# RIO_MCU.net
KiCad netlist of a schematic drawn in Altium Designer
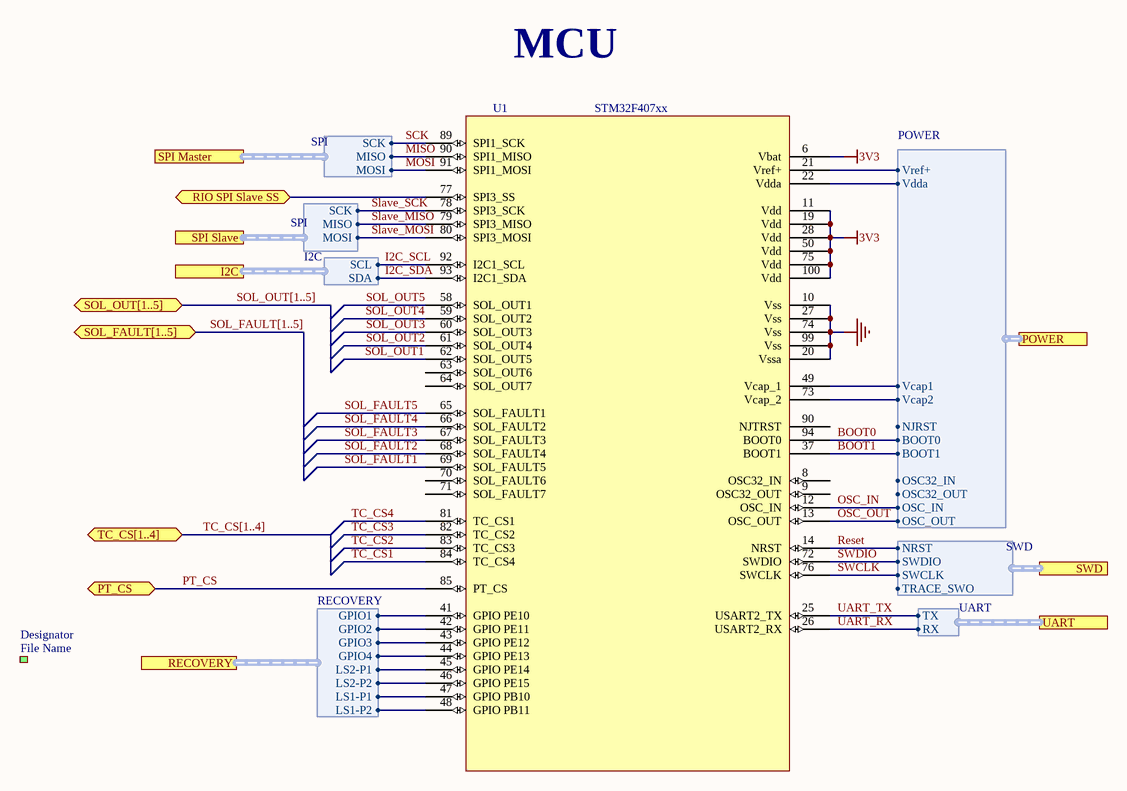
[diagram p0: RIO_MCU.SchDoc]

(export (version "E")
  (design (tool "Eeschema 10.0.6"))
  (components
    (comp (ref "U1")
      (value "STM32F407xx")
      (footprint "LQFP100")
      (libsource (lib "LaunchyRIOComponents") (part "STM32F407xx"))
    )
  )
  (nets
    (net (code "7") (name "/BOOT0") (class "Default")
      (node (ref "U1") (pin "94") (pinfunction "BOOT0_94") (pintype "passive"))
    )
    (net (code "8") (name "/BOOT1") (class "Default")
      (node (ref "U1") (pin "37") (pinfunction "BOOT1_37") (pintype "passive"))
    )
    (net (code "9") (name "/GPIO1") (class "Default")
      (node (ref "U1") (pin "41") (pinfunction "GPIO_PE10_41") (pintype "bidirectional"))
    )
    (net (code "10") (name "/GPIO2") (class "Default")
      (node (ref "U1") (pin "42") (pinfunction "GPIO_PE11_42") (pintype "bidirectional"))
    )
    (net (code "11") (name "/GPIO3") (class "Default")
      (node (ref "U1") (pin "43") (pinfunction "GPIO_PE12_43") (pintype "bidirectional"))
    )
    (net (code "12") (name "/GPIO4") (class "Default")
      (node (ref "U1") (pin "44") (pinfunction "GPIO_PE13_44") (pintype "bidirectional"))
    )
    (net (code "13") (name "/I2C_SCL") (class "Default")
      (node (ref "U1") (pin "92") (pinfunction "I2C1_SCL_92") (pintype "bidirectional"))
    )
    (net (code "14") (name "/I2C_SDA") (class "Default")
      (node (ref "U1") (pin "93") (pinfunction "I2C1_SDA_93") (pintype "bidirectional"))
    )
    (net (code "15") (name "/LS1-P1") (class "Default")
      (node (ref "U1") (pin "47") (pinfunction "GPIO_PB10_47") (pintype "bidirectional"))
    )
    (net (code "16") (name "/LS1-P2") (class "Default")
      (node (ref "U1") (pin "48") (pinfunction "GPIO_PB11_48") (pintype "bidirectional"))
    )
    (net (code "17") (name "/LS2-P1") (class "Default")
      (node (ref "U1") (pin "45") (pinfunction "GPIO_PE14_45") (pintype "bidirectional"))
    )
    (net (code "18") (name "/LS2-P2") (class "Default")
      (node (ref "U1") (pin "46") (pinfunction "GPIO_PE15_46") (pintype "bidirectional"))
    )
    (net (code "19") (name "/MISO") (class "Default")
      (node (ref "U1") (pin "90") (pinfunction "SPI1_MISO_90") (pintype "bidirectional"))
    )
    (net (code "20") (name "/MOSI") (class "Default")
      (node (ref "U1") (pin "91") (pinfunction "SPI1_MOSI_91") (pintype "bidirectional"))
    )
    (net (code "21") (name "/OSC_IN") (class "Default")
      (node (ref "U1") (pin "12") (pinfunction "OSC_IN_12") (pintype "bidirectional"))
    )
    (net (code "22") (name "/OSC_OUT") (class "Default")
      (node (ref "U1") (pin "13") (pinfunction "OSC_OUT_13") (pintype "bidirectional"))
    )
    (net (code "23") (name "/PT_CS") (class "Default")
      (node (ref "U1") (pin "85") (pinfunction "PT_CS_85") (pintype "bidirectional"))
    )
    (net (code "24") (name "/RIO SPI Slave SS") (class "Default")
      (node (ref "U1") (pin "77") (pinfunction "SPI3_SS_77") (pintype "bidirectional"))
    )
    (net (code "25") (name "/Reset") (class "Default")
      (node (ref "U1") (pin "14") (pinfunction "NRST_14") (pintype "bidirectional"))
    )
    (net (code "26") (name "/SCK") (class "Default")
      (node (ref "U1") (pin "89") (pinfunction "SPI1_SCK_89") (pintype "bidirectional"))
    )
    (net (code "27") (name "/SOL_FAULT1") (class "Default")
      (node (ref "U1") (pin "69") (pinfunction "SOL_FAULT5_69") (pintype "bidirectional"))
    )
    (net (code "28") (name "/SOL_FAULT2") (class "Default")
      (node (ref "U1") (pin "68") (pinfunction "SOL_FAULT4_68") (pintype "bidirectional"))
    )
    (net (code "29") (name "/SOL_FAULT3") (class "Default")
      (node (ref "U1") (pin "67") (pinfunction "SOL_FAULT3_67") (pintype "bidirectional"))
    )
    (net (code "30") (name "/SOL_FAULT4") (class "Default")
      (node (ref "U1") (pin "66") (pinfunction "SOL_FAULT2_66") (pintype "bidirectional"))
    )
    (net (code "31") (name "/SOL_FAULT5") (class "Default")
      (node (ref "U1") (pin "65") (pinfunction "SOL_FAULT1_65") (pintype "bidirectional"))
    )
    (net (code "33") (name "/SOL_OUT1") (class "Default")
      (node (ref "U1") (pin "62") (pinfunction "SOL_OUT5_62") (pintype "bidirectional"))
    )
    (net (code "34") (name "/SOL_OUT2") (class "Default")
      (node (ref "U1") (pin "61") (pinfunction "SOL_OUT4_61") (pintype "bidirectional"))
    )
    (net (code "35") (name "/SOL_OUT3") (class "Default")
      (node (ref "U1") (pin "60") (pinfunction "SOL_OUT3_60") (pintype "bidirectional"))
    )
    (net (code "36") (name "/SOL_OUT4") (class "Default")
      (node (ref "U1") (pin "59") (pinfunction "SOL_OUT2_59") (pintype "bidirectional"))
    )
    (net (code "37") (name "/SOL_OUT5") (class "Default")
      (node (ref "U1") (pin "58") (pinfunction "SOL_OUT1_58") (pintype "bidirectional"))
    )
    (net (code "39") (name "/SWCLK") (class "Default")
      (node (ref "U1") (pin "76") (pinfunction "SWCLK_76") (pintype "bidirectional"))
    )
    (net (code "40") (name "/SWDIO") (class "Default")
      (node (ref "U1") (pin "72") (pinfunction "SWDIO_72") (pintype "bidirectional"))
    )
    (net (code "41") (name "/Slave_MISO") (class "Default")
      (node (ref "U1") (pin "79") (pinfunction "SPI3_MISO_79") (pintype "bidirectional"))
    )
    (net (code "42") (name "/Slave_MOSI") (class "Default")
      (node (ref "U1") (pin "80") (pinfunction "SPI3_MOSI_80") (pintype "bidirectional"))
    )
    (net (code "43") (name "/Slave_SCK") (class "Default")
      (node (ref "U1") (pin "78") (pinfunction "SPI3_SCK_78") (pintype "bidirectional"))
    )
    (net (code "44") (name "/TC_CS1") (class "Default")
      (node (ref "U1") (pin "84") (pinfunction "TC_CS4_84") (pintype "bidirectional"))
    )
    (net (code "45") (name "/TC_CS2") (class "Default")
      (node (ref "U1") (pin "83") (pinfunction "TC_CS3_83") (pintype "bidirectional"))
    )
    (net (code "46") (name "/TC_CS3") (class "Default")
      (node (ref "U1") (pin "82") (pinfunction "TC_CS2_82") (pintype "bidirectional"))
    )
    (net (code "47") (name "/TC_CS4") (class "Default")
      (node (ref "U1") (pin "81") (pinfunction "TC_CS1_81") (pintype "bidirectional"))
    )
    (net (code "49") (name "/UART_RX") (class "Default")
      (node (ref "U1") (pin "26") (pinfunction "USART2_RX_26") (pintype "bidirectional"))
    )
    (net (code "50") (name "/UART_TX") (class "Default")
      (node (ref "U1") (pin "25") (pinfunction "USART2_TX_25") (pintype "bidirectional"))
    )
    (net (code "51") (name "/Vcap1") (class "Default")
      (node (ref "U1") (pin "49") (pinfunction "Vcap_1_49") (pintype "passive"))
    )
    (net (code "52") (name "/Vcap2") (class "Default")
      (node (ref "U1") (pin "73") (pinfunction "Vcap_2_73") (pintype "passive"))
    )
    (net (code "53") (name "/Vdda") (class "Default")
      (node (ref "U1") (pin "22") (pinfunction "Vdda_22") (pintype "power_in"))
    )
    (net (code "54") (name "/Vref+") (class "Default")
      (node (ref "U1") (pin "21") (pinfunction "Vref+_21") (pintype "power_in"))
    )
    (net (code "61") (name "3V3") (class "Default")
      (node (ref "U1") (pin "100") (pinfunction "Vdd_100") (pintype "passive"))
      (node (ref "U1") (pin "11") (pinfunction "Vdd_11") (pintype "power_in"))
      (node (ref "U1") (pin "19") (pinfunction "Vdd_19") (pintype "power_in"))
      (node (ref "U1") (pin "28") (pinfunction "Vdd_28") (pintype "power_in"))
      (node (ref "U1") (pin "50") (pinfunction "Vdd_50") (pintype "passive"))
      (node (ref "U1") (pin "6") (pinfunction "Vbat_6") (pintype "power_in"))
      (node (ref "U1") (pin "75") (pinfunction "Vdd_75") (pintype "passive"))
    )
    (net (code "62") (name "GND") (class "Default")
      (node (ref "U1") (pin "10") (pinfunction "Vss_10") (pintype "power_in"))
      (node (ref "U1") (pin "20") (pinfunction "Vssa_20") (pintype "power_in"))
      (node (ref "U1") (pin "27") (pinfunction "Vss_27") (pintype "power_in"))
      (node (ref "U1") (pin "74") (pinfunction "Vss_74") (pintype "power_in"))
      (node (ref "U1") (pin "99") (pinfunction "Vss_99") (pintype "passive"))
    )
    (net (code "63") (name "unconnected-(U1-NJTRST-Pad90)") (class "Default")
      (node (ref "U1") (pin "90") (pinfunction "NJTRST_90") (pintype "passive"))
    )
    (net (code "64") (name "unconnected-(U1-OSC32_IN-Pad8)") (class "Default")
      (node (ref "U1") (pin "8") (pinfunction "OSC32_IN_8") (pintype "bidirectional"))
    )
    (net (code "65") (name "unconnected-(U1-OSC32_OUT-Pad9)") (class "Default")
      (node (ref "U1") (pin "9") (pinfunction "OSC32_OUT_9") (pintype "bidirectional"))
    )
    (net (code "66") (name "unconnected-(U1-SOL_FAULT6-Pad70)") (class "Default")
      (node (ref "U1") (pin "70") (pinfunction "SOL_FAULT6_70") (pintype "bidirectional"))
    )
    (net (code "67") (name "unconnected-(U1-SOL_FAULT7-Pad71)") (class "Default")
      (node (ref "U1") (pin "71") (pinfunction "SOL_FAULT7_71") (pintype "bidirectional"))
    )
    (net (code "68") (name "unconnected-(U1-SOL_OUT6-Pad63)") (class "Default")
      (node (ref "U1") (pin "63") (pinfunction "SOL_OUT6_63") (pintype "bidirectional"))
    )
    (net (code "69") (name "unconnected-(U1-SOL_OUT7-Pad64)") (class "Default")
      (node (ref "U1") (pin "64") (pinfunction "SOL_OUT7_64") (pintype "bidirectional"))
    )
  )
)
